# Main.net
KiCad netlist of a schematic drawn in Altium Designer
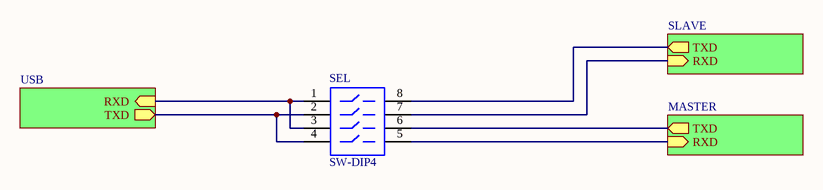
[diagram p0: Main.SchDoc]

(export (version "E")
  (design (tool "Eeschema 10.0.6"))
  (components
    (comp (ref "SEL")
      (value "SW-DIP4")
      (footprint "DIPSW-4-SMD")
      (description "DIP Switch")
      (fields (field (name "PUBLISHER") "Altium Limited"))
      (libsource (lib "Miscellaneous Devices") (part "SW-DIP4"))
    )
  )
  (nets
    (net (code "1") (name "/RXD") (class "Default")
      (node (ref "SEL") (pin "5") (pinfunction "5_5") (pintype "passive"))
    )
    (net (code "2") (name "/RXD_1") (class "Default")
      (node (ref "SEL") (pin "1") (pinfunction "1_1") (pintype "passive"))
      (node (ref "SEL") (pin "3") (pinfunction "3_3") (pintype "passive"))
    )
    (net (code "3") (name "/RXD_2") (class "Default")
      (node (ref "SEL") (pin "7") (pinfunction "7_7") (pintype "passive"))
    )
    (net (code "4") (name "/TXD") (class "Default")
      (node (ref "SEL") (pin "6") (pinfunction "6_6") (pintype "passive"))
    )
    (net (code "5") (name "/TXD_1") (class "Default")
      (node (ref "SEL") (pin "2") (pinfunction "2_2") (pintype "passive"))
      (node (ref "SEL") (pin "4") (pinfunction "4_4") (pintype "passive"))
    )
    (net (code "6") (name "/TXD_2") (class "Default")
      (node (ref "SEL") (pin "8") (pinfunction "8_8") (pintype "passive"))
    )
  )
)
